# DISPLAY.net
KiCad netlist of a schematic drawn in Altium Designer
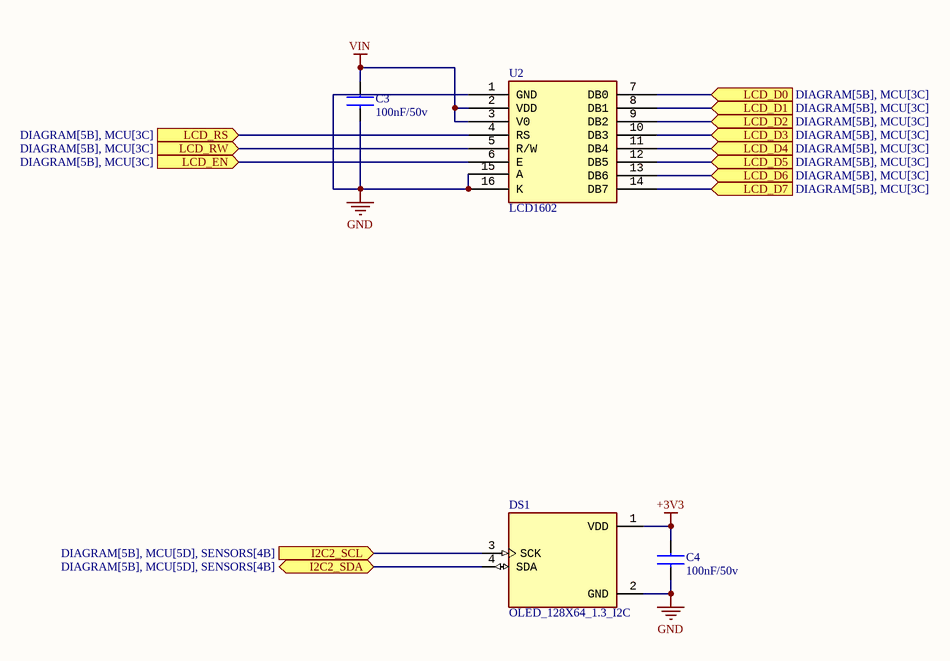
[diagram p0: DISPLAY.SchDoc]

(export (version "E")
  (design (tool "Eeschema 10.0.6"))
  (components
    (comp (ref "C3") (value "100nF/50v") (footprint "CAP-CER-0805") (libsource (lib "ID") (part "CAP-CER")))
    (comp (ref "C4") (value "100nF/50v") (footprint "CAP-CER-0805") (libsource (lib "ID") (part "CAP-CER")))
    (comp (ref "DS1")
      (value "OLED_128X64_1.3_I2C")
      (footprint "LCD_OLED_128X64_1.3_I2C")
      (fields
        (field (name "MF") "UNIVERSAL-SOLDER Electronics Ltd")
        (field (name "MP") "OLED 128x64 1.3&quot; I2C")
        (field (name "MFR# #") "OLED_128X64_1.3_I2C")
      )
      (libsource (lib "Database_Libs1") (part "OLED_128X64_1.3_I2C"))
    )
    (comp (ref "U2") (value "LCD1602") (footprint "LCD16X2") (libsource (lib "ID") (part "LCD1602")))
  )
  (nets
    (net (code "1") (name "+3V3") (class "Default")
      (node (ref "C4") (pin "2") (pinfunction "2_2") (pintype "passive"))
      (node (ref "DS1") (pin "1") (pinfunction "VDD_1") (pintype "power_in"))
    )
    (net (code "2") (name "/I2C2_SCL") (class "Default")
      (node (ref "DS1") (pin "3") (pinfunction "SCK_3") (pintype "input"))
    )
    (net (code "3") (name "/I2C2_SDA") (class "Default")
      (node (ref "DS1") (pin "4") (pinfunction "SDA_4") (pintype "bidirectional"))
    )
    (net (code "4") (name "/LCD_D0") (class "Default")
      (node (ref "U2") (pin "7") (pinfunction "DB0_7") (pintype "passive"))
    )
    (net (code "5") (name "/LCD_D1") (class "Default")
      (node (ref "U2") (pin "8") (pinfunction "DB1_8") (pintype "passive"))
    )
    (net (code "6") (name "/LCD_D2") (class "Default")
      (node (ref "U2") (pin "9") (pinfunction "DB2_9") (pintype "passive"))
    )
    (net (code "7") (name "/LCD_D3") (class "Default")
      (node (ref "U2") (pin "10") (pinfunction "DB3_10") (pintype "passive"))
    )
    (net (code "8") (name "/LCD_D4") (class "Default")
      (node (ref "U2") (pin "11") (pinfunction "DB4_11") (pintype "passive"))
    )
    (net (code "9") (name "/LCD_D5") (class "Default")
      (node (ref "U2") (pin "12") (pinfunction "DB5_12") (pintype "passive"))
    )
    (net (code "10") (name "/LCD_D6") (class "Default")
      (node (ref "U2") (pin "13") (pinfunction "DB6_13") (pintype "passive"))
    )
    (net (code "11") (name "/LCD_D7") (class "Default")
      (node (ref "U2") (pin "14") (pinfunction "DB7_14") (pintype "passive"))
    )
    (net (code "12") (name "/LCD_EN") (class "Default")
      (node (ref "U2") (pin "6") (pinfunction "E_6") (pintype "passive"))
    )
    (net (code "13") (name "/LCD_RS") (class "Default")
      (node (ref "U2") (pin "4") (pinfunction "RS_4") (pintype "passive"))
    )
    (net (code "14") (name "/LCD_RW") (class "Default")
      (node (ref "U2") (pin "5") (pinfunction "R/W_5") (pintype "passive"))
    )
    (net (code "15") (name "GND") (class "Default")
      (node (ref "C3") (pin "1") (pinfunction "1_1") (pintype "passive"))
      (node (ref "C4") (pin "1") (pinfunction "1_1") (pintype "passive"))
      (node (ref "DS1") (pin "2") (pinfunction "GND_2") (pintype "power_in"))
      (node (ref "U2") (pin "1") (pinfunction "GND_1") (pintype "passive"))
      (node (ref "U2") (pin "15") (pinfunction "A_15") (pintype "passive"))
      (node (ref "U2") (pin "16") (pinfunction "K_16") (pintype "passive"))
    )
    (net (code "16") (name "VIN") (class "Default")
      (node (ref "C3") (pin "2") (pinfunction "2_2") (pintype "passive"))
      (node (ref "U2") (pin "2") (pinfunction "VDD_2") (pintype "passive"))
      (node (ref "U2") (pin "3") (pinfunction "V0_3") (pintype "passive"))
    )
  )
)
